# PGTN021_octasource_led_drivers.net
KiCad netlist of a schematic drawn in EAGLE
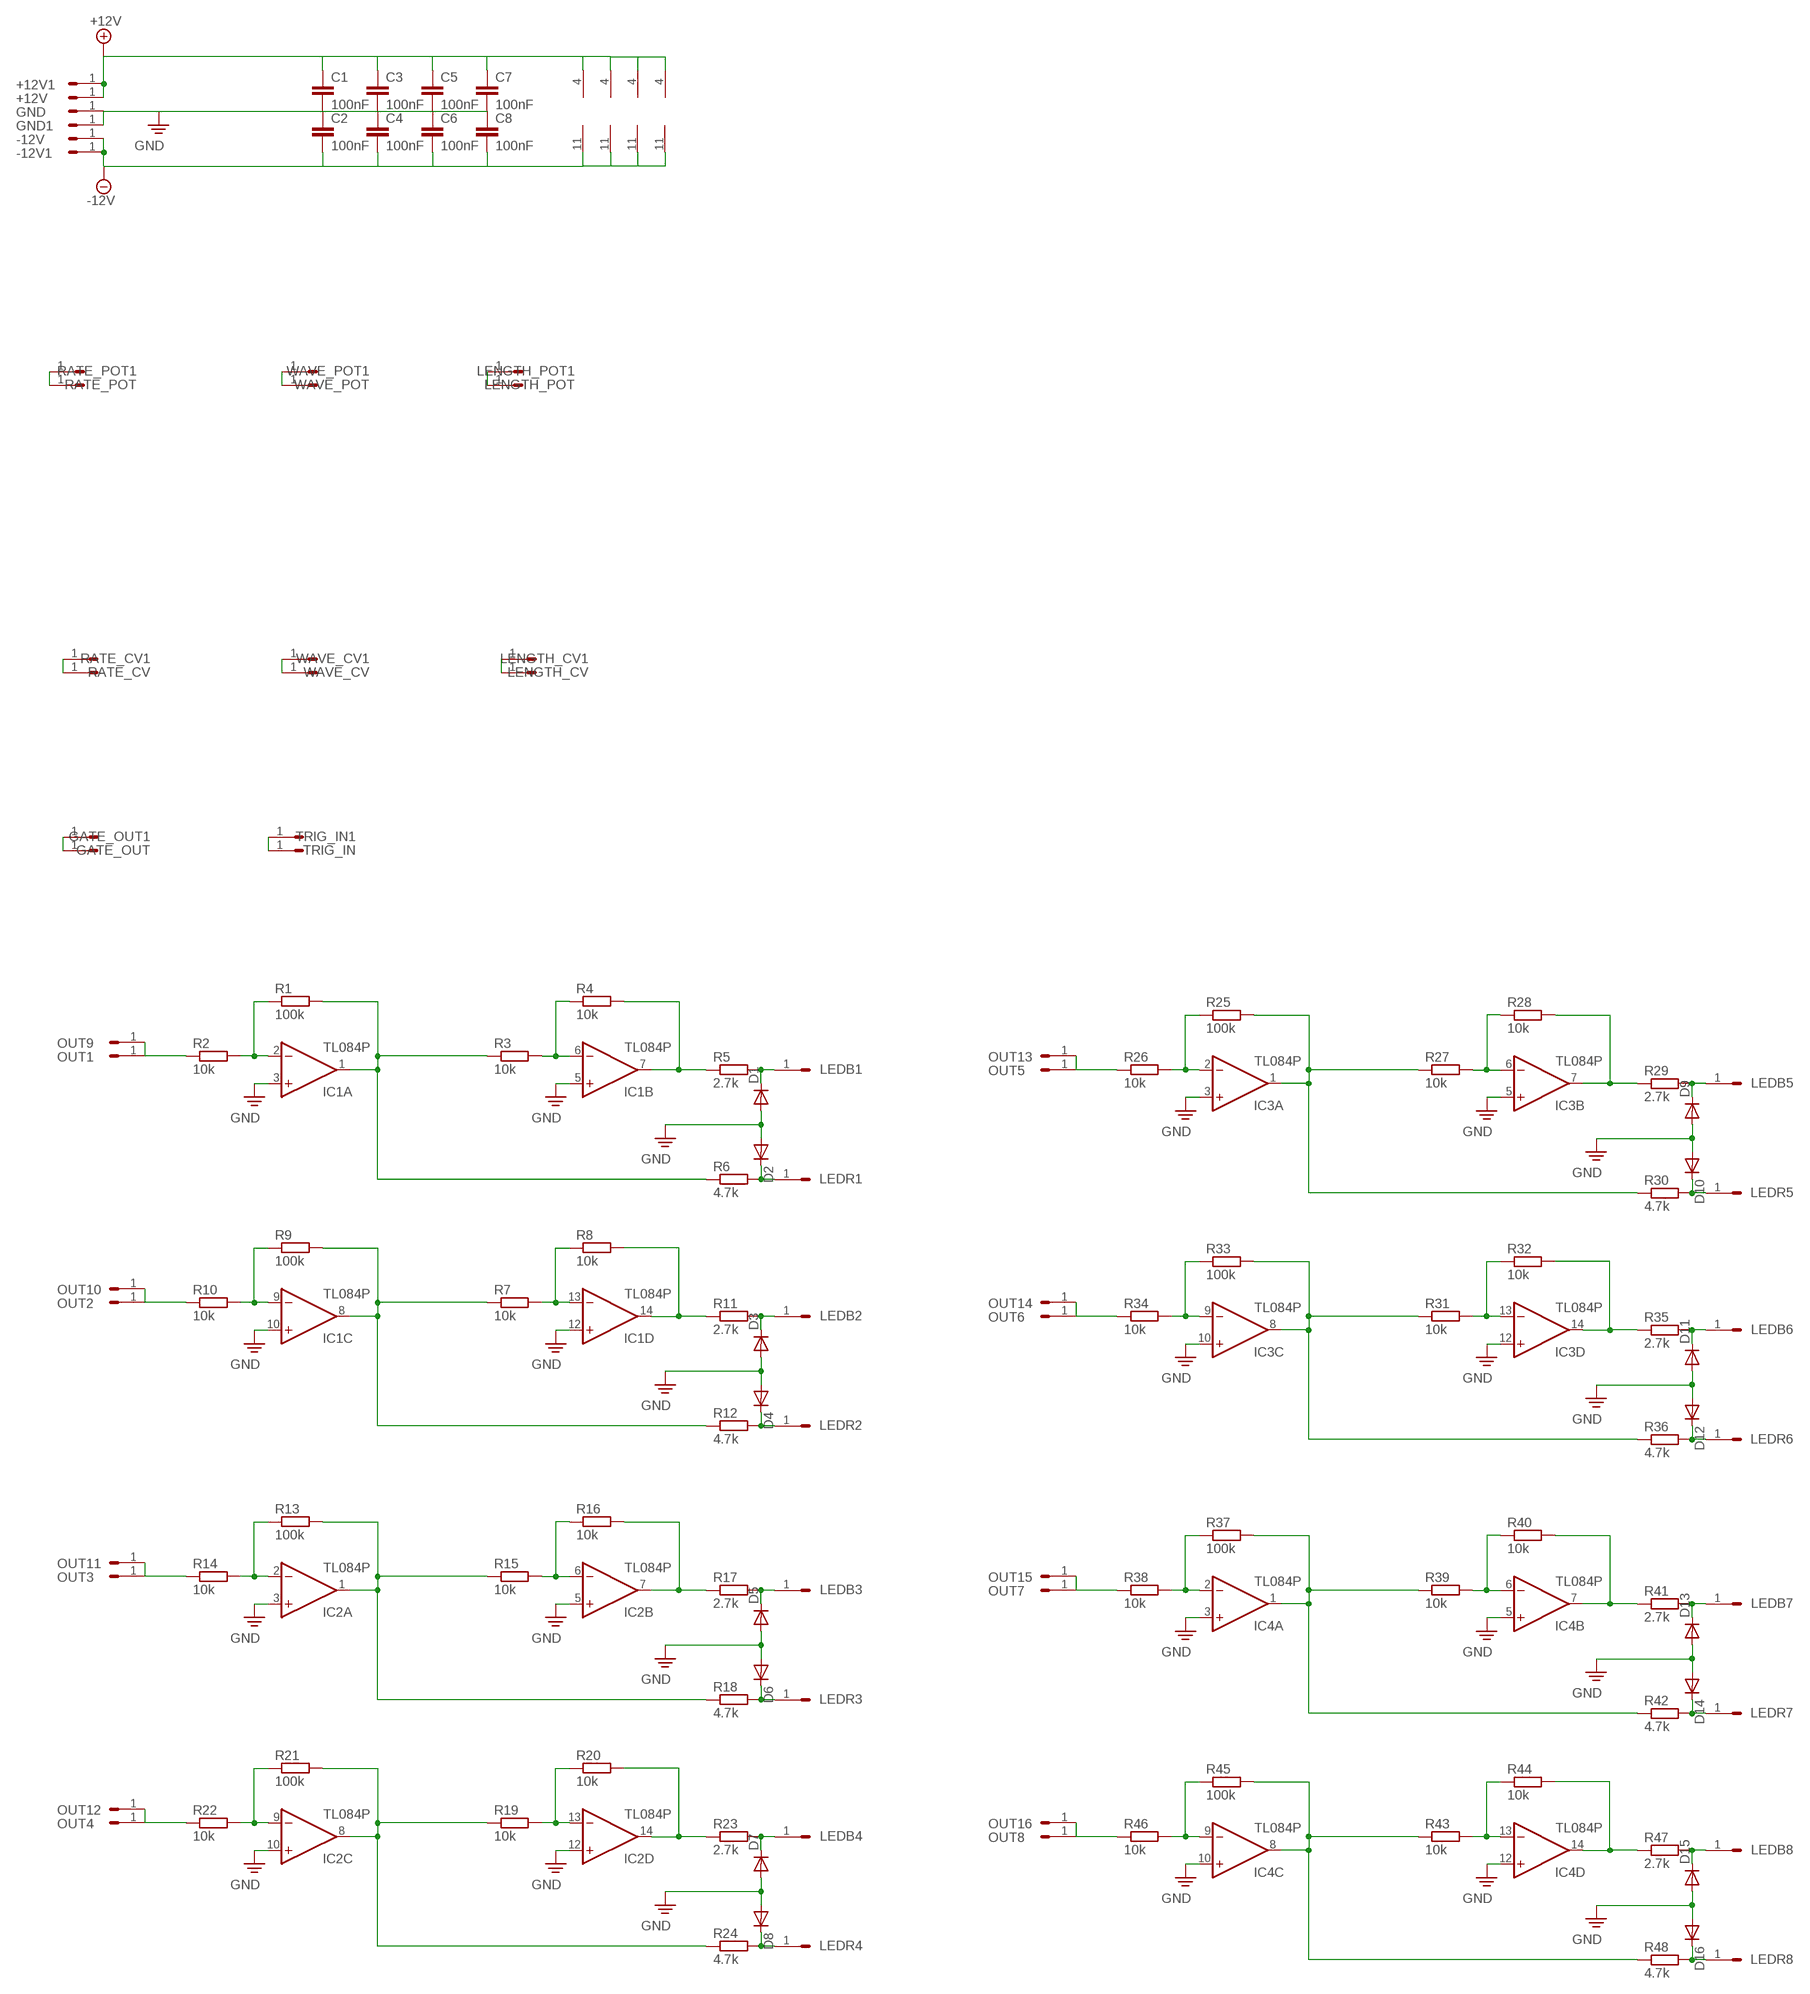
[diagram p0: schematic, sheet 1]

(export (version "E")
  (design (tool "Eeschema 10.0.6"))
  (components
    (comp (ref "+12V")
      (value "HEADER/MALE/01")
      (footprint "eagle-import:HEADER_MALE_01")
      (libsource (lib "eagle-import") (part "HEADER/MALE/01"))
    )
    (comp (ref "+12V1")
      (value "HEADER/MALE/01")
      (footprint "eagle-import:HEADER_MALE_01")
      (libsource (lib "eagle-import") (part "HEADER/MALE/01"))
    )
    (comp (ref "-12V")
      (value "HEADER/MALE/01")
      (footprint "eagle-import:HEADER_MALE_01")
      (libsource (lib "eagle-import") (part "HEADER/MALE/01"))
    )
    (comp (ref "-12V1")
      (value "HEADER/MALE/01")
      (footprint "eagle-import:HEADER_MALE_01")
      (libsource (lib "eagle-import") (part "HEADER/MALE/01"))
    )
    (comp (ref "C1")
      (value "100nF")
      (footprint "eagle-import:CERAMICDISC_5")
      (libsource (lib "eagle-import") (part "CAPACITORCERAMICDISC/5"))
    )
    (comp (ref "C2")
      (value "100nF")
      (footprint "eagle-import:CERAMICDISC_5")
      (libsource (lib "eagle-import") (part "CAPACITORCERAMICDISC/5"))
    )
    (comp (ref "C3")
      (value "100nF")
      (footprint "eagle-import:CERAMICDISC_5")
      (libsource (lib "eagle-import") (part "CAPACITORCERAMICDISC/5"))
    )
    (comp (ref "C4")
      (value "100nF")
      (footprint "eagle-import:CERAMICDISC_5")
      (libsource (lib "eagle-import") (part "CAPACITORCERAMICDISC/5"))
    )
    (comp (ref "C5")
      (value "100nF")
      (footprint "eagle-import:CERAMICDISC_5")
      (libsource (lib "eagle-import") (part "CAPACITORCERAMICDISC/5"))
    )
    (comp (ref "C6")
      (value "100nF")
      (footprint "eagle-import:CERAMICDISC_5")
      (libsource (lib "eagle-import") (part "CAPACITORCERAMICDISC/5"))
    )
    (comp (ref "C7")
      (value "100nF")
      (footprint "eagle-import:CERAMICDISC_5")
      (libsource (lib "eagle-import") (part "CAPACITORCERAMICDISC/5"))
    )
    (comp (ref "C8")
      (value "100nF")
      (footprint "eagle-import:CERAMICDISC_5")
      (libsource (lib "eagle-import") (part "CAPACITORCERAMICDISC/5"))
    )
    (comp (ref "D1")
      (value "1N4148DO35-7")
      (footprint "eagle-import:DO35-7")
      (libsource (lib "eagle-import") (part "1N4148DO35-7"))
    )
    (comp (ref "D2")
      (value "1N4148DO35-7")
      (footprint "eagle-import:DO35-7")
      (libsource (lib "eagle-import") (part "1N4148DO35-7"))
    )
    (comp (ref "D3")
      (value "1N4148DO35-7")
      (footprint "eagle-import:DO35-7")
      (libsource (lib "eagle-import") (part "1N4148DO35-7"))
    )
    (comp (ref "D4")
      (value "1N4148DO35-7")
      (footprint "eagle-import:DO35-7")
      (libsource (lib "eagle-import") (part "1N4148DO35-7"))
    )
    (comp (ref "D5")
      (value "1N4148DO35-7")
      (footprint "eagle-import:DO35-7")
      (libsource (lib "eagle-import") (part "1N4148DO35-7"))
    )
    (comp (ref "D6")
      (value "1N4148DO35-7")
      (footprint "eagle-import:DO35-7")
      (libsource (lib "eagle-import") (part "1N4148DO35-7"))
    )
    (comp (ref "D7")
      (value "1N4148DO35-7")
      (footprint "eagle-import:DO35-7")
      (libsource (lib "eagle-import") (part "1N4148DO35-7"))
    )
    (comp (ref "D8")
      (value "1N4148DO35-7")
      (footprint "eagle-import:DO35-7")
      (libsource (lib "eagle-import") (part "1N4148DO35-7"))
    )
    (comp (ref "D9")
      (value "1N4148DO35-7")
      (footprint "eagle-import:DO35-7")
      (libsource (lib "eagle-import") (part "1N4148DO35-7"))
    )
    (comp (ref "D10")
      (value "1N4148DO35-7")
      (footprint "eagle-import:DO35-7")
      (libsource (lib "eagle-import") (part "1N4148DO35-7"))
    )
    (comp (ref "D11")
      (value "1N4148DO35-7")
      (footprint "eagle-import:DO35-7")
      (libsource (lib "eagle-import") (part "1N4148DO35-7"))
    )
    (comp (ref "D12")
      (value "1N4148DO35-7")
      (footprint "eagle-import:DO35-7")
      (libsource (lib "eagle-import") (part "1N4148DO35-7"))
    )
    (comp (ref "D13")
      (value "1N4148DO35-7")
      (footprint "eagle-import:DO35-7")
      (libsource (lib "eagle-import") (part "1N4148DO35-7"))
    )
    (comp (ref "D14")
      (value "1N4148DO35-7")
      (footprint "eagle-import:DO35-7")
      (libsource (lib "eagle-import") (part "1N4148DO35-7"))
    )
    (comp (ref "D15")
      (value "1N4148DO35-7")
      (footprint "eagle-import:DO35-7")
      (libsource (lib "eagle-import") (part "1N4148DO35-7"))
    )
    (comp (ref "D16")
      (value "1N4148DO35-7")
      (footprint "eagle-import:DO35-7")
      (libsource (lib "eagle-import") (part "1N4148DO35-7"))
    )
    (comp (ref "GATE_OUT")
      (value "HEADER/MALE/01")
      (footprint "eagle-import:HEADER_MALE_01")
      (libsource (lib "eagle-import") (part "HEADER/MALE/01"))
    )
    (comp (ref "GATE_OUT1")
      (value "HEADER/MALE/01")
      (footprint "eagle-import:HEADER_MALE_01")
      (libsource (lib "eagle-import") (part "HEADER/MALE/01"))
    )
    (comp (ref "GND")
      (value "HEADER/MALE/01")
      (footprint "eagle-import:HEADER_MALE_01")
      (libsource (lib "eagle-import") (part "HEADER/MALE/01"))
    )
    (comp (ref "GND1")
      (value "HEADER/MALE/01")
      (footprint "eagle-import:HEADER_MALE_01")
      (libsource (lib "eagle-import") (part "HEADER/MALE/01"))
    )
    (comp (ref "IC1")
      (value "TL084P")
      (footprint "eagle-import:DIL14")
      (libsource (lib "eagle-import") (part "TL084P"))
    )
    (comp (ref "IC2")
      (value "TL084P")
      (footprint "eagle-import:DIL14")
      (libsource (lib "eagle-import") (part "TL084P"))
    )
    (comp (ref "IC3")
      (value "TL084P")
      (footprint "eagle-import:DIL14")
      (libsource (lib "eagle-import") (part "TL084P"))
    )
    (comp (ref "IC4")
      (value "TL084P")
      (footprint "eagle-import:DIL14")
      (libsource (lib "eagle-import") (part "TL084P"))
    )
    (comp (ref "LEDB1")
      (value "HEADER/MALE/01")
      (footprint "eagle-import:HEADER_MALE_01")
      (libsource (lib "eagle-import") (part "HEADER/MALE/01"))
    )
    (comp (ref "LEDB2")
      (value "HEADER/MALE/01")
      (footprint "eagle-import:HEADER_MALE_01")
      (libsource (lib "eagle-import") (part "HEADER/MALE/01"))
    )
    (comp (ref "LEDB3")
      (value "HEADER/MALE/01")
      (footprint "eagle-import:HEADER_MALE_01")
      (libsource (lib "eagle-import") (part "HEADER/MALE/01"))
    )
    (comp (ref "LEDB4")
      (value "HEADER/MALE/01")
      (footprint "eagle-import:HEADER_MALE_01")
      (libsource (lib "eagle-import") (part "HEADER/MALE/01"))
    )
    (comp (ref "LEDB5")
      (value "HEADER/MALE/01")
      (footprint "eagle-import:HEADER_MALE_01")
      (libsource (lib "eagle-import") (part "HEADER/MALE/01"))
    )
    (comp (ref "LEDB6")
      (value "HEADER/MALE/01")
      (footprint "eagle-import:HEADER_MALE_01")
      (libsource (lib "eagle-import") (part "HEADER/MALE/01"))
    )
    (comp (ref "LEDB7")
      (value "HEADER/MALE/01")
      (footprint "eagle-import:HEADER_MALE_01")
      (libsource (lib "eagle-import") (part "HEADER/MALE/01"))
    )
    (comp (ref "LEDB8")
      (value "HEADER/MALE/01")
      (footprint "eagle-import:HEADER_MALE_01")
      (libsource (lib "eagle-import") (part "HEADER/MALE/01"))
    )
    (comp (ref "LEDR1")
      (value "HEADER/MALE/01")
      (footprint "eagle-import:HEADER_MALE_01")
      (libsource (lib "eagle-import") (part "HEADER/MALE/01"))
    )
    (comp (ref "LEDR2")
      (value "HEADER/MALE/01")
      (footprint "eagle-import:HEADER_MALE_01")
      (libsource (lib "eagle-import") (part "HEADER/MALE/01"))
    )
    (comp (ref "LEDR3")
      (value "HEADER/MALE/01")
      (footprint "eagle-import:HEADER_MALE_01")
      (libsource (lib "eagle-import") (part "HEADER/MALE/01"))
    )
    (comp (ref "LEDR4")
      (value "HEADER/MALE/01")
      (footprint "eagle-import:HEADER_MALE_01")
      (libsource (lib "eagle-import") (part "HEADER/MALE/01"))
    )
    (comp (ref "LEDR5")
      (value "HEADER/MALE/01")
      (footprint "eagle-import:HEADER_MALE_01")
      (libsource (lib "eagle-import") (part "HEADER/MALE/01"))
    )
    (comp (ref "LEDR6")
      (value "HEADER/MALE/01")
      (footprint "eagle-import:HEADER_MALE_01")
      (libsource (lib "eagle-import") (part "HEADER/MALE/01"))
    )
    (comp (ref "LEDR7")
      (value "HEADER/MALE/01")
      (footprint "eagle-import:HEADER_MALE_01")
      (libsource (lib "eagle-import") (part "HEADER/MALE/01"))
    )
    (comp (ref "LEDR8")
      (value "HEADER/MALE/01")
      (footprint "eagle-import:HEADER_MALE_01")
      (libsource (lib "eagle-import") (part "HEADER/MALE/01"))
    )
    (comp (ref "LENGTH_CV")
      (value "HEADER/MALE/01")
      (footprint "eagle-import:HEADER_MALE_01")
      (libsource (lib "eagle-import") (part "HEADER/MALE/01"))
    )
    (comp (ref "LENGTH_CV1")
      (value "HEADER/MALE/01")
      (footprint "eagle-import:HEADER_MALE_01")
      (libsource (lib "eagle-import") (part "HEADER/MALE/01"))
    )
    (comp (ref "LENGTH_POT")
      (value "HEADER/MALE/01")
      (footprint "eagle-import:HEADER_MALE_01")
      (libsource (lib "eagle-import") (part "HEADER/MALE/01"))
    )
    (comp (ref "LENGTH_POT1")
      (value "HEADER/MALE/01")
      (footprint "eagle-import:HEADER_MALE_01")
      (libsource (lib "eagle-import") (part "HEADER/MALE/01"))
    )
    (comp (ref "OUT1")
      (value "HEADER/MALE/01")
      (footprint "eagle-import:HEADER_MALE_01")
      (libsource (lib "eagle-import") (part "HEADER/MALE/01"))
    )
    (comp (ref "OUT2")
      (value "HEADER/MALE/01")
      (footprint "eagle-import:HEADER_MALE_01")
      (libsource (lib "eagle-import") (part "HEADER/MALE/01"))
    )
    (comp (ref "OUT3")
      (value "HEADER/MALE/01")
      (footprint "eagle-import:HEADER_MALE_01")
      (libsource (lib "eagle-import") (part "HEADER/MALE/01"))
    )
    (comp (ref "OUT4")
      (value "HEADER/MALE/01")
      (footprint "eagle-import:HEADER_MALE_01")
      (libsource (lib "eagle-import") (part "HEADER/MALE/01"))
    )
    (comp (ref "OUT5")
      (value "HEADER/MALE/01")
      (footprint "eagle-import:HEADER_MALE_01")
      (libsource (lib "eagle-import") (part "HEADER/MALE/01"))
    )
    (comp (ref "OUT6")
      (value "HEADER/MALE/01")
      (footprint "eagle-import:HEADER_MALE_01")
      (libsource (lib "eagle-import") (part "HEADER/MALE/01"))
    )
    (comp (ref "OUT7")
      (value "HEADER/MALE/01")
      (footprint "eagle-import:HEADER_MALE_01")
      (libsource (lib "eagle-import") (part "HEADER/MALE/01"))
    )
    (comp (ref "OUT8")
      (value "HEADER/MALE/01")
      (footprint "eagle-import:HEADER_MALE_01")
      (libsource (lib "eagle-import") (part "HEADER/MALE/01"))
    )
    (comp (ref "OUT9")
      (value "HEADER/MALE/01")
      (footprint "eagle-import:HEADER_MALE_01")
      (libsource (lib "eagle-import") (part "HEADER/MALE/01"))
    )
    (comp (ref "OUT10")
      (value "HEADER/MALE/01")
      (footprint "eagle-import:HEADER_MALE_01")
      (libsource (lib "eagle-import") (part "HEADER/MALE/01"))
    )
    (comp (ref "OUT11")
      (value "HEADER/MALE/01")
      (footprint "eagle-import:HEADER_MALE_01")
      (libsource (lib "eagle-import") (part "HEADER/MALE/01"))
    )
    (comp (ref "OUT12")
      (value "HEADER/MALE/01")
      (footprint "eagle-import:HEADER_MALE_01")
      (libsource (lib "eagle-import") (part "HEADER/MALE/01"))
    )
    (comp (ref "OUT13")
      (value "HEADER/MALE/01")
      (footprint "eagle-import:HEADER_MALE_01")
      (libsource (lib "eagle-import") (part "HEADER/MALE/01"))
    )
    (comp (ref "OUT14")
      (value "HEADER/MALE/01")
      (footprint "eagle-import:HEADER_MALE_01")
      (libsource (lib "eagle-import") (part "HEADER/MALE/01"))
    )
    (comp (ref "OUT15")
      (value "HEADER/MALE/01")
      (footprint "eagle-import:HEADER_MALE_01")
      (libsource (lib "eagle-import") (part "HEADER/MALE/01"))
    )
    (comp (ref "OUT16")
      (value "HEADER/MALE/01")
      (footprint "eagle-import:HEADER_MALE_01")
      (libsource (lib "eagle-import") (part "HEADER/MALE/01"))
    )
    (comp (ref "R1")
      (value "100k")
      (footprint "eagle-import:RESISTOR_7.5")
      (libsource (lib "eagle-import") (part "RESISTORRESISTOR/UPRIGHT/7.5"))
    )
    (comp (ref "R2")
      (value "10k")
      (footprint "eagle-import:RESISTOR_7.5")
      (libsource (lib "eagle-import") (part "RESISTORRESISTOR/UPRIGHT/7.5"))
    )
    (comp (ref "R3")
      (value "10k")
      (footprint "eagle-import:RESISTOR_7.5")
      (libsource (lib "eagle-import") (part "RESISTORRESISTOR/UPRIGHT/7.5"))
    )
    (comp (ref "R4")
      (value "10k")
      (footprint "eagle-import:RESISTOR_7.5")
      (libsource (lib "eagle-import") (part "RESISTORRESISTOR/UPRIGHT/7.5"))
    )
    (comp (ref "R5")
      (value "2.7k")
      (footprint "eagle-import:RESISTOR_7.5")
      (libsource (lib "eagle-import") (part "RESISTORRESISTOR/UPRIGHT/7.5"))
    )
    (comp (ref "R6")
      (value "4.7k")
      (footprint "eagle-import:RESISTOR_7.5")
      (libsource (lib "eagle-import") (part "RESISTORRESISTOR/UPRIGHT/7.5"))
    )
    (comp (ref "R7")
      (value "10k")
      (footprint "eagle-import:RESISTOR_7.5")
      (libsource (lib "eagle-import") (part "RESISTORRESISTOR/UPRIGHT/7.5"))
    )
    (comp (ref "R8")
      (value "10k")
      (footprint "eagle-import:RESISTOR_7.5")
      (libsource (lib "eagle-import") (part "RESISTORRESISTOR/UPRIGHT/7.5"))
    )
    (comp (ref "R9")
      (value "100k")
      (footprint "eagle-import:RESISTOR_7.5")
      (libsource (lib "eagle-import") (part "RESISTORRESISTOR/UPRIGHT/7.5"))
    )
    (comp (ref "R10")
      (value "10k")
      (footprint "eagle-import:RESISTOR_7.5")
      (libsource (lib "eagle-import") (part "RESISTORRESISTOR/UPRIGHT/7.5"))
    )
    (comp (ref "R11")
      (value "2.7k")
      (footprint "eagle-import:RESISTOR_7.5")
      (libsource (lib "eagle-import") (part "RESISTORRESISTOR/UPRIGHT/7.5"))
    )
    (comp (ref "R12")
      (value "4.7k")
      (footprint "eagle-import:RESISTOR_7.5")
      (libsource (lib "eagle-import") (part "RESISTORRESISTOR/UPRIGHT/7.5"))
    )
    (comp (ref "R13")
      (value "100k")
      (footprint "eagle-import:RESISTOR_7.5")
      (libsource (lib "eagle-import") (part "RESISTORRESISTOR/UPRIGHT/7.5"))
    )
    (comp (ref "R14")
      (value "10k")
      (footprint "eagle-import:RESISTOR_7.5")
      (libsource (lib "eagle-import") (part "RESISTORRESISTOR/UPRIGHT/7.5"))
    )
    (comp (ref "R15")
      (value "10k")
      (footprint "eagle-import:RESISTOR_7.5")
      (libsource (lib "eagle-import") (part "RESISTORRESISTOR/UPRIGHT/7.5"))
    )
    (comp (ref "R16")
      (value "10k")
      (footprint "eagle-import:RESISTOR_7.5")
      (libsource (lib "eagle-import") (part "RESISTORRESISTOR/UPRIGHT/7.5"))
    )
    (comp (ref "R17")
      (value "2.7k")
      (footprint "eagle-import:RESISTOR_7.5")
      (libsource (lib "eagle-import") (part "RESISTORRESISTOR/UPRIGHT/7.5"))
    )
    (comp (ref "R18")
      (value "4.7k")
      (footprint "eagle-import:RESISTOR_7.5")
      (libsource (lib "eagle-import") (part "RESISTORRESISTOR/UPRIGHT/7.5"))
    )
    (comp (ref "R19")
      (value "10k")
      (footprint "eagle-import:RESISTOR_7.5")
      (libsource (lib "eagle-import") (part "RESISTORRESISTOR/UPRIGHT/7.5"))
    )
    (comp (ref "R20")
      (value "10k")
      (footprint "eagle-import:RESISTOR_7.5")
      (libsource (lib "eagle-import") (part "RESISTORRESISTOR/UPRIGHT/7.5"))
    )
    (comp (ref "R21")
      (value "100k")
      (footprint "eagle-import:RESISTOR_7.5")
      (libsource (lib "eagle-import") (part "RESISTORRESISTOR/UPRIGHT/7.5"))
    )
    (comp (ref "R22")
      (value "10k")
      (footprint "eagle-import:RESISTOR_7.5")
      (libsource (lib "eagle-import") (part "RESISTORRESISTOR/UPRIGHT/7.5"))
    )
    (comp (ref "R23")
      (value "2.7k")
      (footprint "eagle-import:RESISTOR_7.5")
      (libsource (lib "eagle-import") (part "RESISTORRESISTOR/UPRIGHT/7.5"))
    )
    (comp (ref "R24")
      (value "4.7k")
      (footprint "eagle-import:RESISTOR_7.5")
      (libsource (lib "eagle-import") (part "RESISTORRESISTOR/UPRIGHT/7.5"))
    )
    (comp (ref "R25")
      (value "100k")
      (footprint "eagle-import:RESISTOR_7.5")
      (libsource (lib "eagle-import") (part "RESISTORRESISTOR/UPRIGHT/7.5"))
    )
    (comp (ref "R26")
      (value "10k")
      (footprint "eagle-import:RESISTOR_7.5")
      (libsource (lib "eagle-import") (part "RESISTORRESISTOR/UPRIGHT/7.5"))
    )
    (comp (ref "R27")
      (value "10k")
      (footprint "eagle-import:RESISTOR_7.5")
      (libsource (lib "eagle-import") (part "RESISTORRESISTOR/UPRIGHT/7.5"))
    )
    (comp (ref "R28")
      (value "10k")
      (footprint "eagle-import:RESISTOR_7.5")
      (libsource (lib "eagle-import") (part "RESISTORRESISTOR/UPRIGHT/7.5"))
    )
    (comp (ref "R29")
      (value "2.7k")
      (footprint "eagle-import:RESISTOR_7.5")
      (libsource (lib "eagle-import") (part "RESISTORRESISTOR/UPRIGHT/7.5"))
    )
    (comp (ref "R30")
      (value "4.7k")
      (footprint "eagle-import:RESISTOR_7.5")
      (libsource (lib "eagle-import") (part "RESISTORRESISTOR/UPRIGHT/7.5"))
    )
    (comp (ref "R31")
      (value "10k")
      (footprint "eagle-import:RESISTOR_7.5")
      (libsource (lib "eagle-import") (part "RESISTORRESISTOR/UPRIGHT/7.5"))
    )
    (comp (ref "R32")
      (value "10k")
      (footprint "eagle-import:RESISTOR_7.5")
      (libsource (lib "eagle-import") (part "RESISTORRESISTOR/UPRIGHT/7.5"))
    )
    (comp (ref "R33")
      (value "100k")
      (footprint "eagle-import:RESISTOR_7.5")
      (libsource (lib "eagle-import") (part "RESISTORRESISTOR/UPRIGHT/7.5"))
    )
    (comp (ref "R34")
      (value "10k")
      (footprint "eagle-import:RESISTOR_7.5")
      (libsource (lib "eagle-import") (part "RESISTORRESISTOR/UPRIGHT/7.5"))
    )
    (comp (ref "R35")
      (value "2.7k")
      (footprint "eagle-import:RESISTOR_7.5")
      (libsource (lib "eagle-import") (part "RESISTORRESISTOR/UPRIGHT/7.5"))
    )
    (comp (ref "R36")
      (value "4.7k")
      (footprint "eagle-import:RESISTOR_7.5")
      (libsource (lib "eagle-import") (part "RESISTORRESISTOR/UPRIGHT/7.5"))
    )
    (comp (ref "R37")
      (value "100k")
      (footprint "eagle-import:RESISTOR_7.5")
      (libsource (lib "eagle-import") (part "RESISTORRESISTOR/UPRIGHT/7.5"))
    )
    (comp (ref "R38")
      (value "10k")
      (footprint "eagle-import:RESISTOR_7.5")
      (libsource (lib "eagle-import") (part "RESISTORRESISTOR/UPRIGHT/7.5"))
    )
    (comp (ref "R39")
      (value "10k")
      (footprint "eagle-import:RESISTOR_7.5")
      (libsource (lib "eagle-import") (part "RESISTORRESISTOR/UPRIGHT/7.5"))
    )
    (comp (ref "R40")
      (value "10k")
      (footprint "eagle-import:RESISTOR_7.5")
      (libsource (lib "eagle-import") (part "RESISTORRESISTOR/UPRIGHT/7.5"))
    )
    (comp (ref "R41")
      (value "2.7k")
      (footprint "eagle-import:RESISTOR_7.5")
      (libsource (lib "eagle-import") (part "RESISTORRESISTOR/UPRIGHT/7.5"))
    )
    (comp (ref "R42")
      (value "4.7k")
      (footprint "eagle-import:RESISTOR_7.5")
      (libsource (lib "eagle-import") (part "RESISTORRESISTOR/UPRIGHT/7.5"))
    )
    (comp (ref "R43")
      (value "10k")
      (footprint "eagle-import:RESISTOR_7.5")
      (libsource (lib "eagle-import") (part "RESISTORRESISTOR/UPRIGHT/7.5"))
    )
    (comp (ref "R44")
      (value "10k")
      (footprint "eagle-import:RESISTOR_7.5")
      (libsource (lib "eagle-import") (part "RESISTORRESISTOR/UPRIGHT/7.5"))
    )
    (comp (ref "R45")
      (value "100k")
      (footprint "eagle-import:RESISTOR_7.5")
      (libsource (lib "eagle-import") (part "RESISTORRESISTOR/UPRIGHT/7.5"))
    )
    (comp (ref "R46")
      (value "10k")
      (footprint "eagle-import:RESISTOR_7.5")
      (libsource (lib "eagle-import") (part "RESISTORRESISTOR/UPRIGHT/7.5"))
    )
    (comp (ref "R47")
      (value "2.7k")
      (footprint "eagle-import:RESISTOR_7.5")
      (libsource (lib "eagle-import") (part "RESISTORRESISTOR/UPRIGHT/7.5"))
    )
    (comp (ref "R48")
      (value "4.7k")
      (footprint "eagle-import:RESISTOR_7.5")
      (libsource (lib "eagle-import") (part "RESISTORRESISTOR/UPRIGHT/7.5"))
    )
    (comp (ref "RATE_CV")
      (value "HEADER/MALE/01")
      (footprint "eagle-import:HEADER_MALE_01")
      (libsource (lib "eagle-import") (part "HEADER/MALE/01"))
    )
    (comp (ref "RATE_CV1")
      (value "HEADER/MALE/01")
      (footprint "eagle-import:HEADER_MALE_01")
      (libsource (lib "eagle-import") (part "HEADER/MALE/01"))
    )
    (comp (ref "RATE_POT")
      (value "HEADER/MALE/01")
      (footprint "eagle-import:HEADER_MALE_01")
      (libsource (lib "eagle-import") (part "HEADER/MALE/01"))
    )
    (comp (ref "RATE_POT1")
      (value "HEADER/MALE/01")
      (footprint "eagle-import:HEADER_MALE_01")
      (libsource (lib "eagle-import") (part "HEADER/MALE/01"))
    )
    (comp (ref "TRIG_IN")
      (value "HEADER/MALE/01")
      (footprint "eagle-import:HEADER_MALE_01")
      (libsource (lib "eagle-import") (part "HEADER/MALE/01"))
    )
    (comp (ref "TRIG_IN1")
      (value "HEADER/MALE/01")
      (footprint "eagle-import:HEADER_MALE_01")
      (libsource (lib "eagle-import") (part "HEADER/MALE/01"))
    )
    (comp (ref "WAVE_CV")
      (value "HEADER/MALE/01")
      (footprint "eagle-import:HEADER_MALE_01")
      (libsource (lib "eagle-import") (part "HEADER/MALE/01"))
    )
    (comp (ref "WAVE_CV1")
      (value "HEADER/MALE/01")
      (footprint "eagle-import:HEADER_MALE_01")
      (libsource (lib "eagle-import") (part "HEADER/MALE/01"))
    )
    (comp (ref "WAVE_POT")
      (value "HEADER/MALE/01")
      (footprint "eagle-import:HEADER_MALE_01")
      (libsource (lib "eagle-import") (part "HEADER/MALE/01"))
    )
    (comp (ref "WAVE_POT1")
      (value "HEADER/MALE/01")
      (footprint "eagle-import:HEADER_MALE_01")
      (libsource (lib "eagle-import") (part "HEADER/MALE/01"))
    )
  )
  (nets
    (net (code "1") (name "+12V") (class "Default")
      (node (ref "+12V") (pin "1") (pinfunction "3_1") (pintype "passive"))
      (node (ref "+12V1") (pin "1") (pinfunction "3_1") (pintype "passive"))
      (node (ref "C1") (pin "1") (pinfunction "1_1") (pintype "passive"))
      (node (ref "C3") (pin "1") (pinfunction "1_1") (pintype "passive"))
      (node (ref "C5") (pin "1") (pinfunction "1_1") (pintype "passive"))
      (node (ref "C7") (pin "1") (pinfunction "1_1") (pintype "passive"))
      (node (ref "IC1") (pin "4") (pinfunction "V+_4") (pintype "power_in"))
      (node (ref "IC2") (pin "4") (pinfunction "V+_4") (pintype "power_in"))
      (node (ref "IC3") (pin "4") (pinfunction "V+_4") (pintype "power_in"))
      (node (ref "IC4") (pin "4") (pinfunction "V+_4") (pintype "power_in"))
    )
    (net (code "2") (name "-12V") (class "Default")
      (node (ref "-12V") (pin "1") (pinfunction "3_1") (pintype "passive"))
      (node (ref "-12V1") (pin "1") (pinfunction "3_1") (pintype "passive"))
      (node (ref "C2") (pin "2") (pinfunction "2_2") (pintype "passive"))
      (node (ref "C4") (pin "2") (pinfunction "2_2") (pintype "passive"))
      (node (ref "C6") (pin "2") (pinfunction "2_2") (pintype "passive"))
      (node (ref "C8") (pin "2") (pinfunction "2_2") (pintype "passive"))
      (node (ref "IC1") (pin "11") (pinfunction "V-_11") (pintype "power_in"))
      (node (ref "IC2") (pin "11") (pinfunction "V-_11") (pintype "power_in"))
      (node (ref "IC3") (pin "11") (pinfunction "V-_11") (pintype "power_in"))
      (node (ref "IC4") (pin "11") (pinfunction "V-_11") (pintype "power_in"))
    )
    (net (code "3") (name "GND") (class "Default")
      (node (ref "C1") (pin "2") (pinfunction "2_2") (pintype "passive"))
      (node (ref "C2") (pin "1") (pinfunction "1_1") (pintype "passive"))
      (node (ref "C3") (pin "2") (pinfunction "2_2") (pintype "passive"))
      (node (ref "C4") (pin "1") (pinfunction "1_1") (pintype "passive"))
      (node (ref "C5") (pin "2") (pinfunction "2_2") (pintype "passive"))
      (node (ref "C6") (pin "1") (pinfunction "1_1") (pintype "passive"))
      (node (ref "C7") (pin "2") (pinfunction "2_2") (pintype "passive"))
      (node (ref "C8") (pin "1") (pinfunction "1_1") (pintype "passive"))
      (node (ref "D1") (pin "A") (pinfunction "A_A") (pintype "passive"))
      (node (ref "D10") (pin "A") (pinfunction "A_A") (pintype "passive"))
      (node (ref "D11") (pin "A") (pinfunction "A_A") (pintype "passive"))
      (node (ref "D12") (pin "A") (pinfunction "A_A") (pintype "passive"))
      (node (ref "D13") (pin "A") (pinfunction "A_A") (pintype "passive"))
      (node (ref "D14") (pin "A") (pinfunction "A_A") (pintype "passive"))
      (node (ref "D15") (pin "A") (pinfunction "A_A") (pintype "passive"))
      (node (ref "D16") (pin "A") (pinfunction "A_A") (pintype "passive"))
      (node (ref "D2") (pin "A") (pinfunction "A_A") (pintype "passive"))
      (node (ref "D3") (pin "A") (pinfunction "A_A") (pintype "passive"))
      (node (ref "D4") (pin "A") (pinfunction "A_A") (pintype "passive"))
      (node (ref "D5") (pin "A") (pinfunction "A_A") (pintype "passive"))
      (node (ref "D6") (pin "A") (pinfunction "A_A") (pintype "passive"))
      (node (ref "D7") (pin "A") (pinfunction "A_A") (pintype "passive"))
      (node (ref "D8") (pin "A") (pinfunction "A_A") (pintype "passive"))
      (node (ref "D9") (pin "A") (pinfunction "A_A") (pintype "passive"))
      (node (ref "GND") (pin "1") (pinfunction "3_1") (pintype "passive"))
      (node (ref "GND1") (pin "1") (pinfunction "3_1") (pintype "passive"))
      (node (ref "IC1") (pin "10") (pinfunction "+IN_10") (pintype "input"))
      (node (ref "IC1") (pin "12") (pinfunction "+IN_12") (pintype "input"))
      (node (ref "IC1") (pin "3") (pinfunction "+IN_3") (pintype "input"))
      (node (ref "IC1") (pin "5") (pinfunction "+IN_5") (pintype "input"))
      (node (ref "IC2") (pin "10") (pinfunction "+IN_10") (pintype "input"))
      (node (ref "IC2") (pin "12") (pinfunction "+IN_12") (pintype "input"))
      (node (ref "IC2") (pin "3") (pinfunction "+IN_3") (pintype "input"))
      (node (ref "IC2") (pin "5") (pinfunction "+IN_5") (pintype "input"))
      (node (ref "IC3") (pin "10") (pinfunction "+IN_10") (pintype "input"))
      (node (ref "IC3") (pin "12") (pinfunction "+IN_12") (pintype "input"))
      (node (ref "IC3") (pin "3") (pinfunction "+IN_3") (pintype "input"))
      (node (ref "IC3") (pin "5") (pinfunction "+IN_5") (pintype "input"))
      (node (ref "IC4") (pin "10") (pinfunction "+IN_10") (pintype "input"))
      (node (ref "IC4") (pin "12") (pinfunction "+IN_12") (pintype "input"))
      (node (ref "IC4") (pin "3") (pinfunction "+IN_3") (pintype "input"))
      (node (ref "IC4") (pin "5") (pinfunction "+IN_5") (pintype "input"))
    )
    (net (code "4") (name "Net-(GATE_OUT-3)") (class "Default")
      (node (ref "GATE_OUT") (pin "1") (pinfunction "3_1") (pintype "passive"))
      (node (ref "GATE_OUT1") (pin "1") (pinfunction "3_1") (pintype "passive"))
    )
    (net (code "5") (name "Net-(IC1A--IN)") (class "Default")
      (node (ref "IC1") (pin "2") (pinfunction "-IN_2") (pintype "input"))
      (node (ref "R1") (pin "1") (pinfunction "1_1") (pintype "passive"))
      (node (ref "R2") (pin "2") (pinfunction "2_2") (pintype "passive"))
    )
    (net (code "6") (name "Net-(IC1A-OUT)") (class "Default")
      (node (ref "IC1") (pin "1") (pinfunction "OUT_1") (pintype "output"))
      (node (ref "R1") (pin "2") (pinfunction "2_2") (pintype "passive"))
      (node (ref "R3") (pin "1") (pinfunction "1_1") (pintype "passive"))
      (node (ref "R6") (pin "1") (pinfunction "1_1") (pintype "passive"))
    )
    (net (code "7") (name "Net-(IC1B--IN)") (class "Default")
      (node (ref "IC1") (pin "6") (pinfunction "-IN_6") (pintype "input"))
      (node (ref "R3") (pin "2") (pinfunction "2_2") (pintype "passive"))
      (node (ref "R4") (pin "1") (pinfunction "1_1") (pintype "passive"))
    )
    (net (code "8") (name "Net-(IC1B-OUT)") (class "Default")
      (node (ref "IC1") (pin "7") (pinfunction "OUT_7") (pintype "output"))
      (node (ref "R4") (pin "2") (pinfunction "2_2") (pintype "passive"))
      (node (ref "R5") (pin "1") (pinfunction "1_1") (pintype "passive"))
    )
    (net (code "9") (name "Net-(IC1C--IN)") (class "Default")
      (node (ref "IC1") (pin "9") (pinfunction "-IN_9") (pintype "input"))
      (node (ref "R10") (pin "2") (pinfunction "2_2") (pintype "passive"))
      (node (ref "R9") (pin "1") (pinfunction "1_1") (pintype "passive"))
    )
    (net (code "10") (name "Net-(IC1C-OUT)") (class "Default")
      (node (ref "IC1") (pin "8") (pinfunction "OUT_8") (pintype "output"))
      (node (ref "R12") (pin "1") (pinfunction "1_1") (pintype "passive"))
      (node (ref "R7") (pin "1") (pinfunction "1_1") (pintype "passive"))
      (node (ref "R9") (pin "2") (pinfunction "2_2") (pintype "passive"))
    )
    (net (code "11") (name "Net-(IC1D--IN)") (class "Default")
      (node (ref "IC1") (pin "13") (pinfunction "-IN_13") (pintype "input"))
      (node (ref "R7") (pin "2") (pinfunction "2_2") (pintype "passive"))
      (node (ref "R8") (pin "1") (pinfunction "1_1") (pintype "passive"))
    )
    (net (code "12") (name "Net-(IC1D-OUT)") (class "Default")
      (node (ref "IC1") (pin "14") (pinfunction "OUT_14") (pintype "output"))
      (node (ref "R11") (pin "1") (pinfunction "1_1") (pintype "passive"))
      (node (ref "R8") (pin "2") (pinfunction "2_2") (pintype "passive"))
    )
    (net (code "13") (name "Net-(IC2A--IN)") (class "Default")
      (node (ref "IC2") (pin "2") (pinfunction "-IN_2") (pintype "input"))
      (node (ref "R13") (pin "1") (pinfunction "1_1") (pintype "passive"))
      (node (ref "R14") (pin "2") (pinfunction "2_2") (pintype "passive"))
    )
    (net (code "14") (name "Net-(IC2A-OUT)") (class "Default")
      (node (ref "IC2") (pin "1") (pinfunction "OUT_1") (pintype "output"))
      (node (ref "R13") (pin "2") (pinfunction "2_2") (pintype "passive"))
      (node (ref "R15") (pin "1") (pinfunction "1_1") (pintype "passive"))
      (node (ref "R18") (pin "1") (pinfunction "1_1") (pintype "passive"))
    )
    (net (code "15") (name "Net-(IC2B--IN)") (class "Default")
      (node (ref "IC2") (pin "6") (pinfunction "-IN_6") (pintype "input"))
      (node (ref "R15") (pin "2") (pinfunction "2_2") (pintype "passive"))
      (node (ref "R16") (pin "1") (pinfunction "1_1") (pintype "passive"))
    )
    (net (code "16") (name "Net-(IC2B-OUT)") (class "Default")
      (node (ref "IC2") (pin "7") (pinfunction "OUT_7") (pintype "output"))
      (node (ref "R16") (pin "2") (pinfunction "2_2") (pintype "passive"))
      (node (ref "R17") (pin "1") (pinfunction "1_1") (pintype "passive"))
    )
    (net (code "17") (name "Net-(IC2C--IN)") (class "Default")
      (node (ref "IC2") (pin "9") (pinfunction "-IN_9") (pintype "input"))
      (node (ref "R21") (pin "1") (pinfunction "1_1") (pintype "passive"))
      (node (ref "R22") (pin "2") (pinfunction "2_2") (pintype "passive"))
    )
    (net (code "18") (name "Net-(IC2C-OUT)") (class "Default")
      (node (ref "IC2") (pin "8") (pinfunction "OUT_8") (pintype "output"))
      (node (ref "R19") (pin "1") (pinfunction "1_1") (pintype "passive"))
      (node (ref "R21") (pin "2") (pinfunction "2_2") (pintype "passive"))
      (node (ref "R24") (pin "1") (pinfunction "1_1") (pintype "passive"))
    )
    (net (code "19") (name "Net-(IC2D--IN)") (class "Default")
      (node (ref "IC2") (pin "13") (pinfunction "-IN_13") (pintype "input"))
      (node (ref "R19") (pin "2") (pinfunction "2_2") (pintype "passive"))
      (node (ref "R20") (pin "1") (pinfunction "1_1") (pintype "passive"))
    )
    (net (code "20") (name "Net-(IC2D-OUT)") (class "Default")
      (node (ref "IC2") (pin "14") (pinfunction "OUT_14") (pintype "output"))
      (node (ref "R20") (pin "2") (pinfunction "2_2") (pintype "passive"))
      (node (ref "R23") (pin "1") (pinfunction "1_1") (pintype "passive"))
    )
    (net (code "21") (name "Net-(IC3A--IN)") (class "Default")
      (node (ref "IC3") (pin "2") (pinfunction "-IN_2") (pintype "input"))
      (node (ref "R25") (pin "1") (pinfunction "1_1") (pintype "passive"))
      (node (ref "R26") (pin "2") (pinfunction "2_2") (pintype "passive"))
    )
    (net (code "22") (name "Net-(IC3A-OUT)") (class "Default")
      (node (ref "IC3") (pin "1") (pinfunction "OUT_1") (pintype "output"))
      (node (ref "R25") (pin "2") (pinfunction "2_2") (pintype "passive"))
      (node (ref "R27") (pin "1") (pinfunction "1_1") (pintype "passive"))
      (node (ref "R30") (pin "1") (pinfunction "1_1") (pintype "passive"))
    )
    (net (code "23") (name "Net-(IC3B--IN)") (class "Default")
      (node (ref "IC3") (pin "6") (pinfunction "-IN_6") (pintype "input"))
      (node (ref "R27") (pin "2") (pinfunction "2_2") (pintype "passive"))
      (node (ref "R28") (pin "1") (pinfunction "1_1") (pintype "passive"))
    )
    (net (code "24") (name "Net-(IC3B-OUT)") (class "Default")
      (node (ref "IC3") (pin "7") (pinfunction "OUT_7") (pintype "output"))
      (node (ref "R28") (pin "2") (pinfunction "2_2") (pintype "passive"))
      (node (ref "R29") (pin "1") (pinfunction "1_1") (pintype "passive"))
    )
    (net (code "25") (name "Net-(IC3C--IN)") (class "Default")
      (node (ref "IC3") (pin "9") (pinfunction "-IN_9") (pintype "input"))
      (node (ref "R33") (pin "1") (pinfunction "1_1") (pintype "passive"))
      (node (ref "R34") (pin "2") (pinfunction "2_2") (pintype "passive"))
    )
    (net (code "26") (name "Net-(IC3C-OUT)") (class "Default")
      (node (ref "IC3") (pin "8") (pinfunction "OUT_8") (pintype "output"))
      (node (ref "R31") (pin "1") (pinfunction "1_1") (pintype "passive"))
      (node (ref "R33") (pin "2") (pinfunction "2_2") (pintype "passive"))
      (node (ref "R36") (pin "1") (pinfunction "1_1") (pintype "passive"))
    )
    (net (code "27") (name "Net-(IC3D--IN)") (class "Default")
      (node (ref "IC3") (pin "13") (pinfunction "-IN_13") (pintype "input"))
      (node (ref "R31") (pin "2") (pinfunction "2_2") (pintype "passive"))
      (node (ref "R32") (pin "1") (pinfunction "1_1") (pintype "passive"))
    )
    (net (code "28") (name "Net-(IC3D-OUT)") (class "Default")
      (node (ref "IC3") (pin "14") (pinfunction "OUT_14") (pintype "output"))
      (node (ref "R32") (pin "2") (pinfunction "2_2") (pintype "passive"))
      (node (ref "R35") (pin "1") (pinfunction "1_1") (pintype "passive"))
    )
    (net (code "29") (name "Net-(IC4A--IN)") (class "Default")
      (node (ref "IC4") (pin "2") (pinfunction "-IN_2") (pintype "input"))
      (node (ref "R37") (pin "1") (pinfunction "1_1") (pintype "passive"))
      (node (ref "R38") (pin "2") (pinfunction "2_2") (pintype "passive"))
    )
    (net (code "30") (name "Net-(IC4A-OUT)") (class "Default")
      (node (ref "IC4") (pin "1") (pinfunction "OUT_1") (pintype "output"))
      (node (ref "R37") (pin "2") (pinfunction "2_2") (pintype "passive"))
      (node (ref "R39") (pin "1") (pinfunction "1_1") (pintype "passive"))
      (node (ref "R42") (pin "1") (pinfunction "1_1") (pintype "passive"))
    )
    (net (code "31") (name "Net-(IC4B--IN)") (class "Default")
      (node (ref "IC4") (pin "6") (pinfunction "-IN_6") (pintype "input"))
      (node (ref "R39") (pin "2") (pinfunction "2_2") (pintype "passive"))
      (node (ref "R40") (pin "1") (pinfunction "1_1") (pintype "passive"))
    )
    (net (code "32") (name "Net-(IC4B-OUT)") (class "Default")
      (node (ref "IC4") (pin "7") (pinfunction "OUT_7") (pintype "output"))
      (node (ref "R40") (pin "2") (pinfunction "2_2") (pintype "passive"))
      (node (ref "R41") (pin "1") (pinfunction "1_1") (pintype "passive"))
    )
    (net (code "33") (name "Net-(IC4C--IN)") (class "Default")
      (node (ref "IC4") (pin "9") (pinfunction "-IN_9") (pintype "input"))
      (node (ref "R45") (pin "1") (pinfunction "1_1") (pintype "passive"))
      (node (ref "R46") (pin "2") (pinfunction "2_2") (pintype "passive"))
    )
    (net (code "34") (name "Net-(IC4C-OUT)") (class "Default")
      (node (ref "IC4") (pin "8") (pinfunction "OUT_8") (pintype "output"))
      (node (ref "R43") (pin "1") (pinfunction "1_1") (pintype "passive"))
      (node (ref "R45") (pin "2") (pinfunction "2_2") (pintype "passive"))
      (node (ref "R48") (pin "1") (pinfunction "1_1") (pintype "passive"))
    )
    (net (code "35") (name "Net-(IC4D--IN)") (class "Default")
      (node (ref "IC4") (pin "13") (pinfunction "-IN_13") (pintype "input"))
      (node (ref "R43") (pin "2") (pinfunction "2_2") (pintype "passive"))
      (node (ref "R44") (pin "1") (pinfunction "1_1") (pintype "passive"))
    )
    (net (code "36") (name "Net-(IC4D-OUT)") (class "Default")
      (node (ref "IC4") (pin "14") (pinfunction "OUT_14") (pintype "output"))
      (node (ref "R44") (pin "2") (pinfunction "2_2") (pintype "passive"))
      (node (ref "R47") (pin "1") (pinfunction "1_1") (pintype "passive"))
    )
    (net (code "37") (name "Net-(LEDB1-3)") (class "Default")
      (node (ref "D1") (pin "C") (pinfunction "C_C") (pintype "passive"))
      (node (ref "LEDB1") (pin "1") (pinfunction "3_1") (pintype "passive"))
      (node (ref "R5") (pin "2") (pinfunction "2_2") (pintype "passive"))
    )
    (net (code "38") (name "Net-(LEDB2-3)") (class "Default")
      (node (ref "D3") (pin "C") (pinfunction "C_C") (pintype "passive"))
      (node (ref "LEDB2") (pin "1") (pinfunction "3_1") (pintype "passive"))
      (node (ref "R11") (pin "2") (pinfunction "2_2") (pintype "passive"))
    )
    (net (code "39") (name "Net-(LEDB3-3)") (class "Default")
      (node (ref "D5") (pin "C") (pinfunction "C_C") (pintype "passive"))
      (node (ref "LEDB3") (pin "1") (pinfunction "3_1") (pintype "passive"))
      (node (ref "R17") (pin "2") (pinfunction "2_2") (pintype "passive"))
    )
    (net (code "40") (name "Net-(LEDB4-3)") (class "Default")
      (node (ref "D7") (pin "C") (pinfunction "C_C") (pintype "passive"))
      (node (ref "LEDB4") (pin "1") (pinfunction "3_1") (pintype "passive"))
      (node (ref "R23") (pin "2") (pinfunction "2_2") (pintype "passive"))
    )
    (net (code "41") (name "Net-(LEDB5-3)") (class "Default")
      (node (ref "D9") (pin "C") (pinfunction "C_C") (pintype "passive"))
      (node (ref "LEDB5") (pin "1") (pinfunction "3_1") (pintype "passive"))
      (node (ref "R29") (pin "2") (pinfunction "2_2") (pintype "passive"))
    )
    (net (code "42") (name "Net-(LEDB6-3)") (class "Default")
      (node (ref "D11") (pin "C") (pinfunction "C_C") (pintype "passive"))
      (node (ref "LEDB6") (pin "1") (pinfunction "3_1") (pintype "passive"))
      (node (ref "R35") (pin "2") (pinfunction "2_2") (pintype "passive"))
    )
    (net (code "43") (name "Net-(LEDB7-3)") (class "Default")
      (node (ref "D13") (pin "C") (pinfunction "C_C") (pintype "passive"))
      (node (ref "LEDB7") (pin "1") (pinfunction "3_1") (pintype "passive"))
      (node (ref "R41") (pin "2") (pinfunction "2_2") (pintype "passive"))
    )
    (net (code "44") (name "Net-(LEDB8-3)") (class "Default")
      (node (ref "D15") (pin "C") (pinfunction "C_C") (pintype "passive"))
      (node (ref "LEDB8") (pin "1") (pinfunction "3_1") (pintype "passive"))
      (node (ref "R47") (pin "2") (pinfunction "2_2") (pintype "passive"))
    )
    (net (code "45") (name "Net-(LEDR1-3)") (class "Default")
      (node (ref "D2") (pin "C") (pinfunction "C_C") (pintype "passive"))
      (node (ref "LEDR1") (pin "1") (pinfunction "3_1") (pintype "passive"))
      (node (ref "R6") (pin "2") (pinfunction "2_2") (pintype "passive"))
    )
    (net (code "46") (name "Net-(LEDR2-3)") (class "Default")
      (node (ref "D4") (pin "C") (pinfunction "C_C") (pintype "passive"))
      (node (ref "LEDR2") (pin "1") (pinfunction "3_1") (pintype "passive"))
      (node (ref "R12") (pin "2") (pinfunction "2_2") (pintype "passive"))
    )
    (net (code "47") (name "Net-(LEDR3-3)") (class "Default")
      (node (ref "D6") (pin "C") (pinfunction "C_C") (pintype "passive"))
      (node (ref "LEDR3") (pin "1") (pinfunction "3_1") (pintype "passive"))
      (node (ref "R18") (pin "2") (pinfunction "2_2") (pintype "passive"))
    )
    (net (code "48") (name "Net-(LEDR4-3)") (class "Default")
      (node (ref "D8") (pin "C") (pinfunction "C_C") (pintype "passive"))
      (node (ref "LEDR4") (pin "1") (pinfunction "3_1") (pintype "passive"))
      (node (ref "R24") (pin "2") (pinfunction "2_2") (pintype "passive"))
    )
    (net (code "49") (name "Net-(LEDR5-3)") (class "Default")
      (node (ref "D10") (pin "C") (pinfunction "C_C") (pintype "passive"))
      (node (ref "LEDR5") (pin "1") (pinfunction "3_1") (pintype "passive"))
      (node (ref "R30") (pin "2") (pinfunction "2_2") (pintype "passive"))
    )
    (net (code "50") (name "Net-(LEDR6-3)") (class "Default")
      (node (ref "D12") (pin "C") (pinfunction "C_C") (pintype "passive"))
      (node (ref "LEDR6") (pin "1") (pinfunction "3_1") (pintype "passive"))
      (node (ref "R36") (pin "2") (pinfunction "2_2") (pintype "passive"))
    )
    (net (code "51") (name "Net-(LEDR7-3)") (class "Default")
      (node (ref "D14") (pin "C") (pinfunction "C_C") (pintype "passive"))
      (node (ref "LEDR7") (pin "1") (pinfunction "3_1") (pintype "passive"))
      (node (ref "R42") (pin "2") (pinfunction "2_2") (pintype "passive"))
    )
    (net (code "52") (name "Net-(LEDR8-3)") (class "Default")
      (node (ref "D16") (pin "C") (pinfunction "C_C") (pintype "passive"))
      (node (ref "LEDR8") (pin "1") (pinfunction "3_1") (pintype "passive"))
      (node (ref "R48") (pin "2") (pinfunction "2_2") (pintype "passive"))
    )
    (net (code "53") (name "Net-(LENGTH_CV-3)") (class "Default")
      (node (ref "LENGTH_CV") (pin "1") (pinfunction "3_1") (pintype "passive"))
      (node (ref "LENGTH_CV1") (pin "1") (pinfunction "3_1") (pintype "passive"))
    )
    (net (code "54") (name "Net-(LENGTH_POT-3)") (class "Default")
      (node (ref "LENGTH_POT") (pin "1") (pinfunction "3_1") (pintype "passive"))
      (node (ref "LENGTH_POT1") (pin "1") (pinfunction "3_1") (pintype "passive"))
    )
    (net (code "55") (name "Net-(OUT1-3)") (class "Default")
      (node (ref "OUT1") (pin "1") (pinfunction "3_1") (pintype "passive"))
      (node (ref "OUT9") (pin "1") (pinfunction "3_1") (pintype "passive"))
      (node (ref "R2") (pin "1") (pinfunction "1_1") (pintype "passive"))
    )
    (net (code "56") (name "Net-(OUT10-3)") (class "Default")
      (node (ref "OUT10") (pin "1") (pinfunction "3_1") (pintype "passive"))
      (node (ref "OUT2") (pin "1") (pinfunction "3_1") (pintype "passive"))
      (node (ref "R10") (pin "1") (pinfunction "1_1") (pintype "passive"))
    )
    (net (code "57") (name "Net-(OUT11-3)") (class "Default")
      (node (ref "OUT11") (pin "1") (pinfunction "3_1") (pintype "passive"))
      (node (ref "OUT3") (pin "1") (pinfunction "3_1") (pintype "passive"))
      (node (ref "R14") (pin "1") (pinfunction "1_1") (pintype "passive"))
    )
    (net (code "58") (name "Net-(OUT12-3)") (class "Default")
      (node (ref "OUT12") (pin "1") (pinfunction "3_1") (pintype "passive"))
      (node (ref "OUT4") (pin "1") (pinfunction "3_1") (pintype "passive"))
      (node (ref "R22") (pin "1") (pinfunction "1_1") (pintype "passive"))
    )
    (net (code "59") (name "Net-(OUT13-3)") (class "Default")
      (node (ref "OUT13") (pin "1") (pinfunction "3_1") (pintype "passive"))
      (node (ref "OUT5") (pin "1") (pinfunction "3_1") (pintype "passive"))
      (node (ref "R26") (pin "1") (pinfunction "1_1") (pintype "passive"))
    )
    (net (code "60") (name "Net-(OUT14-3)") (class "Default")
      (node (ref "OUT14") (pin "1") (pinfunction "3_1") (pintype "passive"))
      (node (ref "OUT6") (pin "1") (pinfunction "3_1") (pintype "passive"))
      (node (ref "R34") (pin "1") (pinfunction "1_1") (pintype "passive"))
    )
    (net (code "61") (name "Net-(OUT15-3)") (class "Default")
      (node (ref "OUT15") (pin "1") (pinfunction "3_1") (pintype "passive"))
      (node (ref "OUT7") (pin "1") (pinfunction "3_1") (pintype "passive"))
      (node (ref "R38") (pin "1") (pinfunction "1_1") (pintype "passive"))
    )
    (net (code "62") (name "Net-(OUT16-3)") (class "Default")
      (node (ref "OUT16") (pin "1") (pinfunction "3_1") (pintype "passive"))
      (node (ref "OUT8") (pin "1") (pinfunction "3_1") (pintype "passive"))
      (node (ref "R46") (pin "1") (pinfunction "1_1") (pintype "passive"))
    )
    (net (code "63") (name "Net-(RATE_CV-3)") (class "Default")
      (node (ref "RATE_CV") (pin "1") (pinfunction "3_1") (pintype "passive"))
      (node (ref "RATE_CV1") (pin "1") (pinfunction "3_1") (pintype "passive"))
    )
    (net (code "64") (name "Net-(RATE_POT-3)") (class "Default")
      (node (ref "RATE_POT") (pin "1") (pinfunction "3_1") (pintype "passive"))
      (node (ref "RATE_POT1") (pin "1") (pinfunction "3_1") (pintype "passive"))
    )
    (net (code "65") (name "Net-(TRIG_IN-3)") (class "Default")
      (node (ref "TRIG_IN") (pin "1") (pinfunction "3_1") (pintype "passive"))
      (node (ref "TRIG_IN1") (pin "1") (pinfunction "3_1") (pintype "passive"))
    )
    (net (code "66") (name "Net-(WAVE_CV-3)") (class "Default")
      (node (ref "WAVE_CV") (pin "1") (pinfunction "3_1") (pintype "passive"))
      (node (ref "WAVE_CV1") (pin "1") (pinfunction "3_1") (pintype "passive"))
    )
    (net (code "67") (name "Net-(WAVE_POT-3)") (class "Default")
      (node (ref "WAVE_POT") (pin "1") (pinfunction "3_1") (pintype "passive"))
      (node (ref "WAVE_POT1") (pin "1") (pinfunction "3_1") (pintype "passive"))
    )
  )
)
